# Power_REV_2.net
KiCad netlist of a schematic drawn in Altium Designer
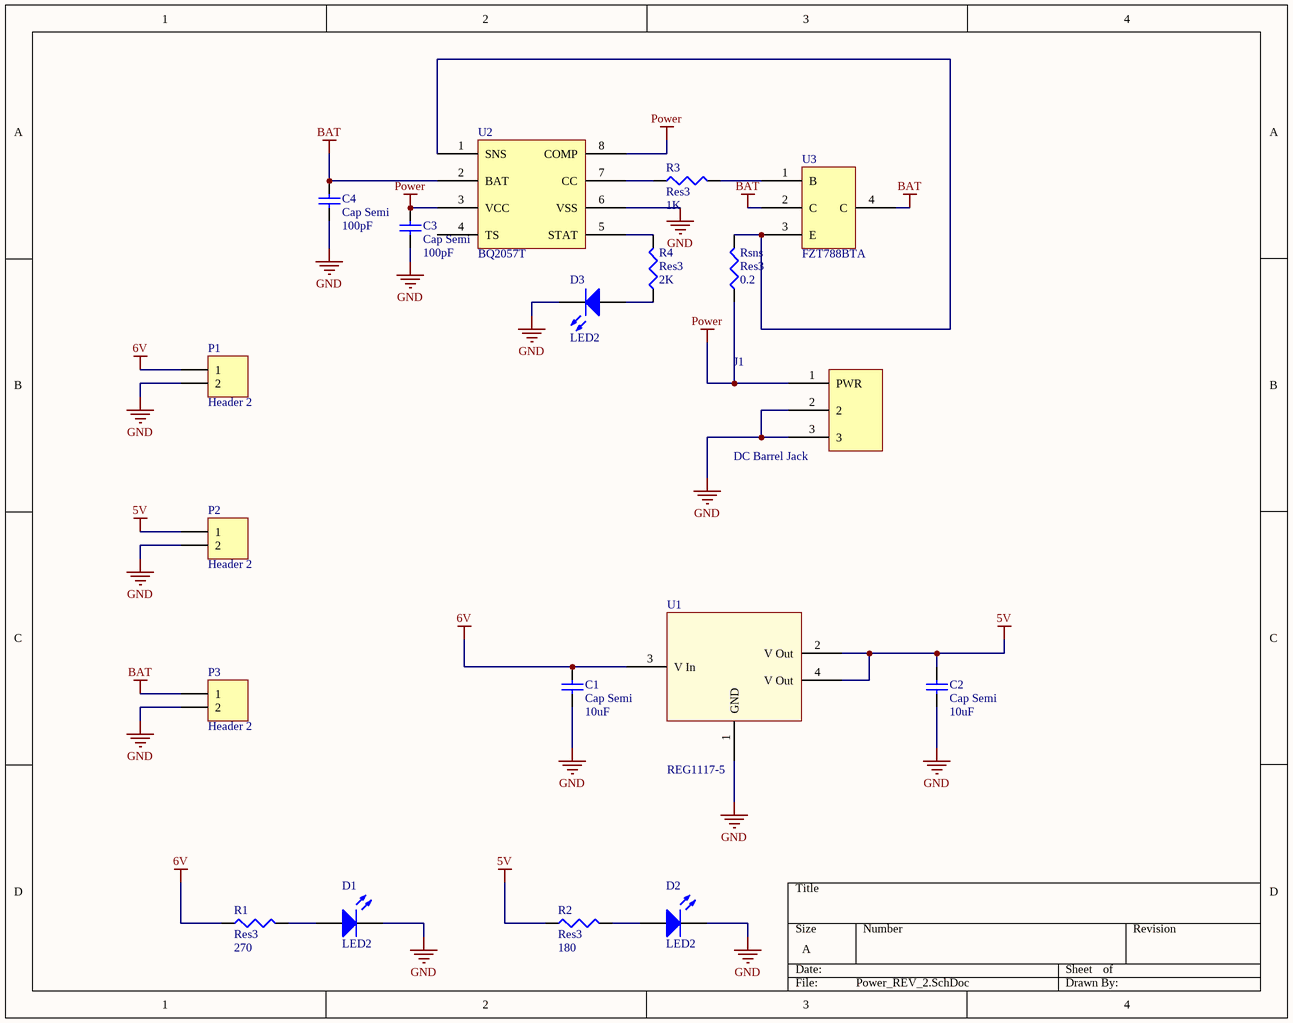
[diagram p0: Power_REV_2.SchDoc]

(export (version "E")
  (design (tool "Eeschema 10.0.6"))
  (components
    (comp (ref "C1")
      (value "Cap Semi")
      (footprint "C1206")
      (description "Capacitor (Semiconductor SIM Model)")
      (fields (field (name "ALTIUM_VALUE") "10uF") (field (name "PUBLISHER") "Altium Limited"))
      (libsource (lib "Miscellaneous Devices") (part "Cap Semi"))
    )
    (comp (ref "C2")
      (value "Cap Semi")
      (footprint "C1206")
      (description "Capacitor (Semiconductor SIM Model)")
      (fields (field (name "ALTIUM_VALUE") "10uF") (field (name "PUBLISHER") "Altium Limited"))
      (libsource (lib "Miscellaneous Devices") (part "Cap Semi"))
    )
    (comp (ref "C3")
      (value "Cap Semi")
      (footprint "C1206")
      (description "Capacitor (Semiconductor SIM Model)")
      (fields (field (name "ALTIUM_VALUE") "100pF") (field (name "PUBLISHER") "Altium Limited"))
      (libsource (lib "Miscellaneous Devices") (part "Cap Semi"))
    )
    (comp (ref "C4")
      (value "Cap Semi")
      (footprint "C1206")
      (description "Capacitor (Semiconductor SIM Model)")
      (fields (field (name "ALTIUM_VALUE") "100pF") (field (name "PUBLISHER") "Altium Limited"))
      (libsource (lib "Miscellaneous Devices") (part "Cap Semi"))
    )
    (comp (ref "D1")
      (value "LED2")
      (footprint "3.2X1.6X1.1")
      (description "Typical RED, GREEN, YELLOW, AMBER GaAs LED")
      (fields (field (name "PUBLISHER") "Altium Limited"))
      (libsource (lib "Miscellaneous Devices") (part "LED2"))
    )
    (comp (ref "D2")
      (value "LED2")
      (footprint "3.2X1.6X1.1")
      (description "Typical RED, GREEN, YELLOW, AMBER GaAs LED")
      (fields (field (name "PUBLISHER") "Altium Limited"))
      (libsource (lib "Miscellaneous Devices") (part "LED2"))
    )
    (comp (ref "D3")
      (value "LED2")
      (footprint "3.2X1.6X1.1")
      (description "Typical RED, GREEN, YELLOW, AMBER GaAs LED")
      (fields (field (name "PUBLISHER") "Altium Limited"))
      (libsource (lib "Miscellaneous Devices") (part "LED2"))
    )
    (comp (ref "J1")
      (value "DC Barrel Jack")
      (footprint "SCKT/SM4.5-2H4")
      (libsource (lib "DC Barrel Jack") (part "DC Barrel Jack"))
    )
    (comp (ref "P1")
      (value "Header 2")
      (footprint "HDR1X2")
      (description "Header, 2-Pin")
      (fields (field (name "PUBLISHER") "Altium Limited"))
      (libsource (lib "Miscellaneous Connectors") (part "Header 2"))
    )
    (comp (ref "P2")
      (value "Header 2")
      (footprint "HDR1X2")
      (description "Header, 2-Pin")
      (fields (field (name "PUBLISHER") "Altium Limited"))
      (libsource (lib "Miscellaneous Connectors") (part "Header 2"))
    )
    (comp (ref "P3")
      (value "Header 2")
      (footprint "HDR1X2")
      (description "Header, 2-Pin")
      (fields (field (name "PUBLISHER") "Altium Limited"))
      (libsource (lib "Miscellaneous Connectors") (part "Header 2"))
    )
    (comp (ref "R1")
      (value "Res3")
      (footprint "J1-0603")
      (description "Resistor")
      (fields (field (name "ALTIUM_VALUE") "270") (field (name "PUBLISHER") "Altium Limited"))
      (libsource (lib "Miscellaneous Devices") (part "Res3"))
    )
    (comp (ref "R2")
      (value "Res3")
      (footprint "J1-0603")
      (description "Resistor")
      (fields (field (name "ALTIUM_VALUE") "180") (field (name "PUBLISHER") "Altium Limited"))
      (libsource (lib "Miscellaneous Devices") (part "Res3"))
    )
    (comp (ref "R3")
      (value "Res3")
      (footprint "J1-0603")
      (description "Resistor")
      (fields (field (name "ALTIUM_VALUE") "1K") (field (name "PUBLISHER") "Altium Limited"))
      (libsource (lib "Miscellaneous Devices") (part "Res3"))
    )
    (comp (ref "R4")
      (value "Res3")
      (footprint "J1-0603")
      (description "Resistor")
      (fields (field (name "ALTIUM_VALUE") "2K") (field (name "PUBLISHER") "Altium Limited"))
      (libsource (lib "Miscellaneous Devices") (part "Res3"))
    )
    (comp (ref "Rsns")
      (value "Res3")
      (footprint "J1-0603")
      (description "Resistor")
      (fields (field (name "ALTIUM_VALUE") "0.2") (field (name "PUBLISHER") "Altium Limited"))
      (libsource (lib "Miscellaneous Devices") (part "Res3"))
    )
    (comp (ref "U1")
      (value "REG1117-5")
      (footprint "SOT230P700X180-4N")
      (libsource (lib "REG1117-5") (part "REG1117-5"))
    )
    (comp (ref "U2")
      (value "BQ2057T")
      (footprint "SOIC127P600X178-8N")
      (libsource (lib "BQ2057T") (part "BQ2057T"))
    )
    (comp (ref "U3")
      (value "FZT788BTA")
      (footprint "SOT230P700X180-4N")
      (libsource (lib "FZT788BTA") (part "FZT788BTA"))
    )
  )
  (nets
    (net (code "1") (name "5V") (class "Default")
      (node (ref "C2") (pin "2") (pinfunction "2_2") (pintype "passive"))
      (node (ref "P2") (pin "1") (pinfunction "1_1") (pintype "passive"))
      (node (ref "R2") (pin "1") (pinfunction "1_1") (pintype "passive"))
      (node (ref "U1") (pin "2") (pinfunction "V_Out_2") (pintype "passive"))
      (node (ref "U1") (pin "4") (pinfunction "V_Out_4") (pintype "passive"))
    )
    (net (code "2") (name "6V") (class "Default")
      (node (ref "C1") (pin "2") (pinfunction "2_2") (pintype "passive"))
      (node (ref "P1") (pin "1") (pinfunction "1_1") (pintype "passive"))
      (node (ref "R1") (pin "1") (pinfunction "1_1") (pintype "passive"))
      (node (ref "U1") (pin "3") (pinfunction "V_In_3") (pintype "passive"))
    )
    (net (code "3") (name "BAT") (class "Default")
      (node (ref "C4") (pin "2") (pinfunction "2_2") (pintype "passive"))
      (node (ref "P3") (pin "1") (pinfunction "1_1") (pintype "passive"))
      (node (ref "U2") (pin "2") (pinfunction "BAT_2") (pintype "passive"))
      (node (ref "U3") (pin "2") (pinfunction "C_2") (pintype "passive"))
      (node (ref "U3") (pin "4") (pinfunction "C_4") (pintype "passive"))
    )
    (net (code "4") (name "GND") (class "Default")
      (node (ref "C1") (pin "1") (pinfunction "1_1") (pintype "passive"))
      (node (ref "C2") (pin "1") (pinfunction "1_1") (pintype "passive"))
      (node (ref "C3") (pin "1") (pinfunction "1_1") (pintype "passive"))
      (node (ref "C4") (pin "1") (pinfunction "1_1") (pintype "passive"))
      (node (ref "D1") (pin "2") (pinfunction "K_2") (pintype "passive"))
      (node (ref "D2") (pin "2") (pinfunction "K_2") (pintype "passive"))
      (node (ref "D3") (pin "2") (pinfunction "K_2") (pintype "passive"))
      (node (ref "J1") (pin "2") (pinfunction "2_2") (pintype "passive"))
      (node (ref "J1") (pin "3") (pinfunction "3_3") (pintype "passive"))
      (node (ref "P1") (pin "2") (pinfunction "2_2") (pintype "passive"))
      (node (ref "P2") (pin "2") (pinfunction "2_2") (pintype "passive"))
      (node (ref "P3") (pin "2") (pinfunction "2_2") (pintype "passive"))
      (node (ref "U1") (pin "1") (pinfunction "GND_1") (pintype "passive"))
      (node (ref "U2") (pin "6") (pinfunction "VSS_6") (pintype "passive"))
    )
    (net (code "5") (name "Net-(D1-A)") (class "Default")
      (node (ref "D1") (pin "1") (pinfunction "A_1") (pintype "passive"))
      (node (ref "R1") (pin "2") (pinfunction "2_2") (pintype "passive"))
    )
    (net (code "6") (name "Net-(D2-A)") (class "Default")
      (node (ref "D2") (pin "1") (pinfunction "A_1") (pintype "passive"))
      (node (ref "R2") (pin "2") (pinfunction "2_2") (pintype "passive"))
    )
    (net (code "7") (name "Net-(D3-A)") (class "Default")
      (node (ref "D3") (pin "1") (pinfunction "A_1") (pintype "passive"))
      (node (ref "R4") (pin "1") (pinfunction "1_1") (pintype "passive"))
    )
    (net (code "8") (name "Net-(U2-CC)") (class "Default")
      (node (ref "R3") (pin "1") (pinfunction "1_1") (pintype "passive"))
      (node (ref "U2") (pin "7") (pinfunction "CC_7") (pintype "passive"))
    )
    (net (code "9") (name "Net-(U2-SNS)") (class "Default")
      (node (ref "Rsns") (pin "2") (pinfunction "2_2") (pintype "passive"))
      (node (ref "U2") (pin "1") (pinfunction "SNS_1") (pintype "passive"))
      (node (ref "U3") (pin "3") (pinfunction "E_3") (pintype "passive"))
    )
    (net (code "10") (name "Net-(U2-STAT)") (class "Default")
      (node (ref "R4") (pin "2") (pinfunction "2_2") (pintype "passive"))
      (node (ref "U2") (pin "5") (pinfunction "STAT_5") (pintype "passive"))
    )
    (net (code "11") (name "Net-(U3-B)") (class "Default")
      (node (ref "R3") (pin "2") (pinfunction "2_2") (pintype "passive"))
      (node (ref "U3") (pin "1") (pinfunction "B_1") (pintype "passive"))
    )
    (net (code "12") (name "Power") (class "Default")
      (node (ref "C3") (pin "2") (pinfunction "2_2") (pintype "passive"))
      (node (ref "J1") (pin "1") (pinfunction "PWR_1") (pintype "passive"))
      (node (ref "Rsns") (pin "1") (pinfunction "1_1") (pintype "passive"))
      (node (ref "U2") (pin "3") (pinfunction "VCC_3") (pintype "passive"))
      (node (ref "U2") (pin "8") (pinfunction "COMP_8") (pintype "passive"))
    )
    (net (code "13") (name "unconnected-(U2-TS-Pad4)") (class "Default")
      (node (ref "U2") (pin "4") (pinfunction "TS_4") (pintype "passive"))
    )
  )
)
